# microphone_adapter_top.net
KiCad netlist of a schematic drawn in Altium Designer
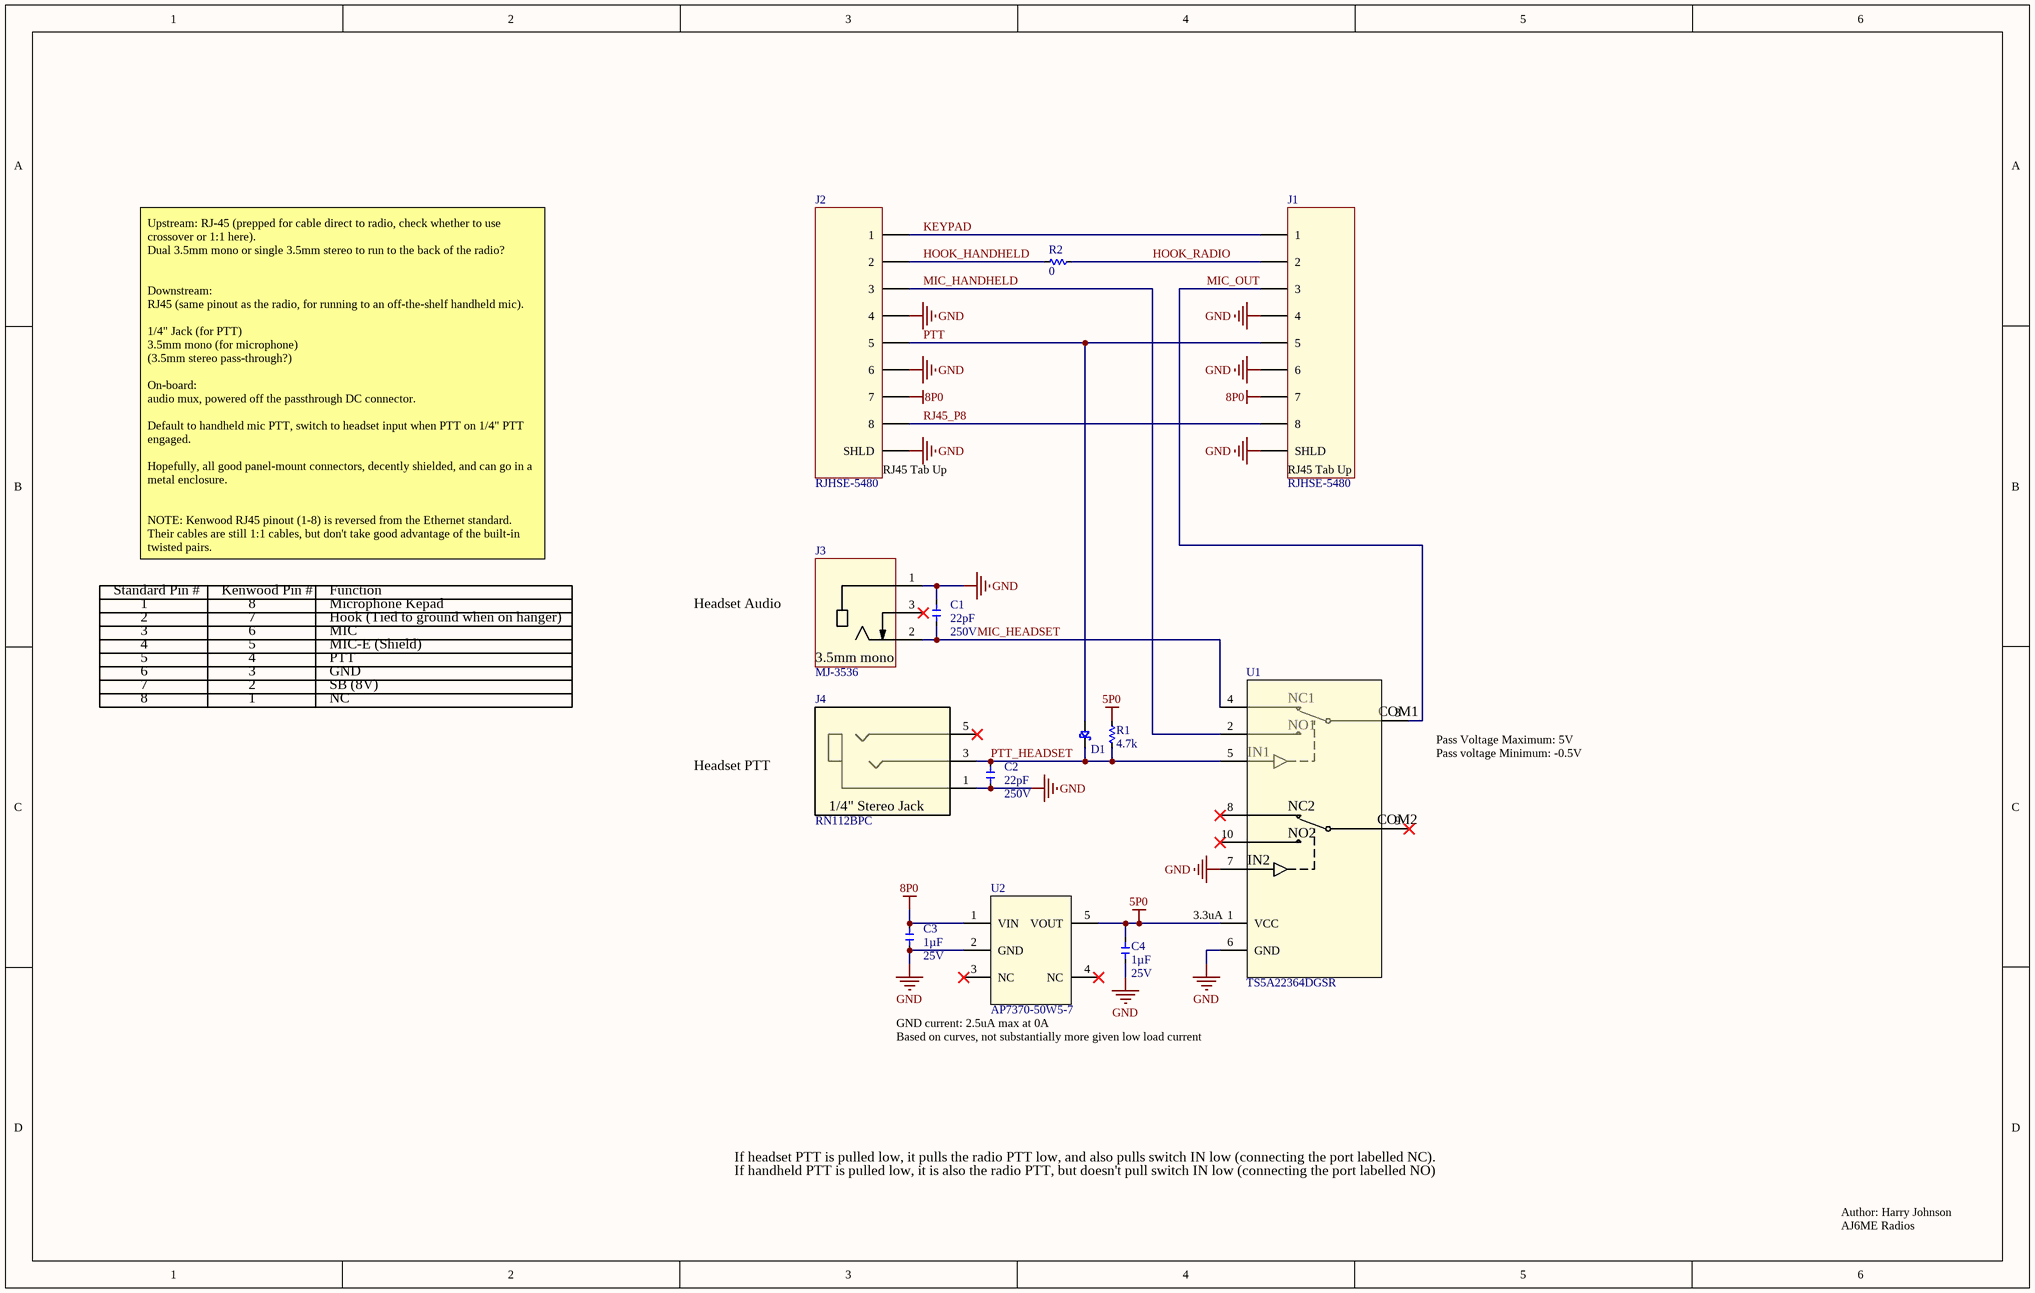
[diagram p0: microphone_adapter_top.SchDoc]

(export (version "E")
  (design (tool "Eeschema 10.0.6"))
  (components
    (comp (ref "C1")
      (value "GRM21A5C2E220JW01D")
      (footprint "C0805_1.00MM")
      (description "CAP CER 22PF 250V C0G/NP0 0805")
      (fields
        (field (name "CAPACITANCE") "22pF")
        (field (name "VOLTAGE - RATED") "250V")
        (field (name "DIGI-KEY PART NUMBER") "490-5534-1-ND")
        (field (name "MANUFACTURER") "Murata Electronics")
      )
      (libsource (lib "passives") (part "2pin_nonpolar_capacitor"))
    )
    (comp (ref "C2")
      (value "GRM21A5C2E220JW01D")
      (footprint "C0805_1.00MM")
      (description "CAP CER 22PF 250V C0G/NP0 0805")
      (fields
        (field (name "CAPACITANCE") "22pF")
        (field (name "VOLTAGE - RATED") "250V")
        (field (name "DIGI-KEY PART NUMBER") "490-5534-1-ND")
        (field (name "MANUFACTURER") "Murata Electronics")
      )
      (libsource (lib "passives") (part "2pin_nonpolar_capacitor"))
    )
    (comp (ref "C3")
      (value "GRM155C81E105ME11D")
      (footprint "C0402_0.55MM")
      (description "CAP CER 1UF 25V X6S 0402")
      (fields
        (field (name "CAPACITANCE") "1µF")
        (field (name "VOLTAGE - RATED") "25V")
        (field (name "DIGI-KEY PART NUMBER") "490-10015-1-ND")
        (field (name "MANUFACTURER") "Murata Electronics")
      )
      (libsource (lib "passives") (part "2pin_nonpolar_capacitor"))
    )
    (comp (ref "C4")
      (value "GRM155C81E105ME11D")
      (footprint "C0402_0.55MM")
      (description "CAP CER 1UF 25V X6S 0402")
      (fields
        (field (name "CAPACITANCE") "1µF")
        (field (name "VOLTAGE - RATED") "25V")
        (field (name "DIGI-KEY PART NUMBER") "490-10015-1-ND")
        (field (name "MANUFACTURER") "Murata Electronics")
      )
      (libsource (lib "passives") (part "2pin_nonpolar_capacitor"))
    )
    (comp (ref "D1")
      (value "BAT54XV2T1G")
      (footprint "SOD523_ONSEMI")
      (description "ON Semi BAT54XV2T1G; SMT Schottky Diode; 30V 200mA; 5ns; 2-Pin SOD-523")
      (fields (field (name "MANUFACTURER") "ON Semiconductor"))
      (libsource (lib "library") (part "DIODE_SCHOTTKY_30V_100MA_BAT54XV2T1G"))
    )
    (comp (ref "J1")
      (value "RJHSE-5480")
      (footprint "ETH_RJ45_RA_RJHSE-5480")
      (description "Conn RJ-45 F 8 POS 2.03mm Solder RA Thru-Hole 8 Terminal 1 Port Tray Cat 5")
      (fields (field (name "MANUFACTURER") "Amphenol"))
      (libsource (lib "") (part "CONN_ETH_RJ45_RA_SHLD_RJHSE-5480_ALT_1"))
    )
    (comp (ref "J2")
      (value "RJHSE-5480")
      (footprint "ETH_RJ45_RA_RJHSE-5480")
      (description "Conn RJ-45 F 8 POS 2.03mm Solder RA Thru-Hole 8 Terminal 1 Port Tray Cat 5")
      (fields (field (name "MANUFACTURER") "Amphenol"))
      (libsource (lib "library") (part "CONN_ETH_RJ45_RA_SHLD_RJHSE-5480_ALT"))
    )
    (comp (ref "J3")
      (value "MJ-3536")
      (footprint "AUD_CUI_MJ-3536")
      (description "CONN JACK MONO 3.5MM R/A")
      (fields (field (name "MANUFACTURER") "CUI"))
      (libsource (lib "library") (part "CONN_AUD_3.5_MM_MONO_MJ-3536"))
    )
    (comp (ref "J4")
      (value "RN112BPC")
      (footprint "AUD_SWITCHCRAFT_RN112BPC")
      (description "CONN JACK STEREO 0.25\" (6.35MM) R/A")
      (fields (field (name "MANUFACTURER") "Switchcraft"))
      (libsource (lib "library") (part "CONN_AUD_250_MIL_RN112BPC"))
    )
    (comp (ref "R1")
      (value "RC0402FR-074K7L")
      (footprint "R0402_0.40MM")
      (description "RES SMD 4.7K OHM 1% 1/16W 0402")
      (fields
        (field (name "RESISTANCE") "4.7k")
        (field (name "DIGI-KEY PART NUMBER") "311-4.7KLRCT-ND")
        (field (name "MANUFACTURER") "Yageo")
      )
      (libsource (lib "passives") (part "2pin_resistor"))
    )
    (comp (ref "R2")
      (value "RC0402JR-070RL")
      (footprint "R0402_0.40MM")
      (description "RES SMD 0 OHM JUMPER 1/16W 0402")
      (fields
        (field (name "RESISTANCE") "0")
        (field (name "DIGI-KEY PART NUMBER") "311-0.0JRCT-ND")
        (field (name "MANUFACTURER") "Yageo")
      )
      (libsource (lib "passives") (part "2pin_resistor"))
    )
    (comp (ref "U1")
      (value "TS5A22364DGSR")
      (footprint "TI_VSSOP_10_DGS0010A")
      (description "TEXAS INSTRUMENTS         TS5A22364DGSR.             ANALOG SWITCH, DUAL, SPDT, MSOP-10")
      (fields (field (name "MANUFACTURER") "Texas Instruments"))
      (libsource (lib "library") (part "IC_ANALOG_SWITCH_DUAL_SPDT_TS5A22364DGSR"))
    )
    (comp (ref "U2")
      (value "AP7370-50W5-7")
      (footprint "DIODES_INC_SOT25_5")
      (description "LDO Regulator Pos 5V 0.3A 5-Pin SOT-25 T/R")
      (fields (field (name "MANUFACTURER") "Diodes"))
      (libsource (lib "library") (part "LDO_5V_AP7370-50W5-7"))
    )
  )
  (nets
    (net (code "1") (name "/HOOK_HANDHELD") (class "Default")
      (node (ref "J2") (pin "2") (pinfunction "2_2") (pintype "passive"))
      (node (ref "R2") (pin "1") (pintype "passive"))
    )
    (net (code "2") (name "/HOOK_RADIO") (class "Default")
      (node (ref "J1") (pin "2") (pinfunction "2_2") (pintype "passive"))
      (node (ref "R2") (pin "2") (pintype "passive"))
    )
    (net (code "3") (name "/KEYPAD") (class "Default")
      (node (ref "J1") (pin "1") (pinfunction "1_1") (pintype "passive"))
      (node (ref "J2") (pin "1") (pinfunction "1_1") (pintype "passive"))
    )
    (net (code "4") (name "/MIC_HANDHELD") (class "Default")
      (node (ref "J2") (pin "3") (pinfunction "3_3") (pintype "passive"))
      (node (ref "U1") (pin "2") (pinfunction "NO1_2") (pintype "passive"))
    )
    (net (code "5") (name "/MIC_HEADSET") (class "Default")
      (node (ref "C1") (pin "2") (pintype "passive"))
      (node (ref "J3") (pin "2") (pinfunction "2_2") (pintype "passive"))
      (node (ref "U1") (pin "4") (pinfunction "NC1_4") (pintype "passive"))
    )
    (net (code "6") (name "/MIC_OUT") (class "Default")
      (node (ref "J1") (pin "3") (pinfunction "3_3") (pintype "passive"))
      (node (ref "U1") (pin "3") (pinfunction "COM1_3") (pintype "passive"))
    )
    (net (code "7") (name "/PTT") (class "Default")
      (node (ref "D1") (pin "2") (pintype "passive"))
      (node (ref "J1") (pin "5") (pinfunction "5_5") (pintype "passive"))
      (node (ref "J2") (pin "5") (pinfunction "5_5") (pintype "passive"))
    )
    (net (code "8") (name "/PTT_HEADSET") (class "Default")
      (node (ref "C2") (pin "1") (pintype "passive"))
      (node (ref "D1") (pin "1") (pintype "passive"))
      (node (ref "J4") (pin "3") (pinfunction "T_3") (pintype "passive"))
      (node (ref "R1") (pin "2") (pintype "passive"))
      (node (ref "U1") (pin "5") (pinfunction "IN1_5") (pintype "passive"))
    )
    (net (code "9") (name "/RJ45_P8") (class "Default")
      (node (ref "J1") (pin "8") (pinfunction "8_8") (pintype "passive"))
      (node (ref "J2") (pin "8") (pinfunction "8_8") (pintype "passive"))
    )
    (net (code "10") (name "5P0") (class "Default")
      (node (ref "C4") (pin "1") (pintype "passive"))
      (node (ref "R1") (pin "1") (pintype "passive"))
      (node (ref "U1") (pin "1") (pinfunction "VCC_1") (pintype "passive"))
      (node (ref "U2") (pin "5") (pinfunction "VOUT_5") (pintype "passive"))
    )
    (net (code "11") (name "8P0") (class "Default")
      (node (ref "C3") (pin "1") (pintype "passive"))
      (node (ref "J1") (pin "7") (pinfunction "7_7") (pintype "passive"))
      (node (ref "J2") (pin "7") (pinfunction "7_7") (pintype "passive"))
      (node (ref "U2") (pin "1") (pinfunction "VIN_1") (pintype "passive"))
    )
    (net (code "12") (name "GND") (class "Default")
      (node (ref "C1") (pin "1") (pintype "passive"))
      (node (ref "C2") (pin "2") (pintype "passive"))
      (node (ref "C3") (pin "2") (pintype "passive"))
      (node (ref "C4") (pin "2") (pintype "passive"))
      (node (ref "J1") (pin "4") (pinfunction "4_4") (pintype "passive"))
      (node (ref "J1") (pin "6") (pinfunction "6_6") (pintype "passive"))
      (node (ref "J1") (pin "SHLD") (pinfunction "SHLD_SHLD") (pintype "passive"))
      (node (ref "J2") (pin "4") (pinfunction "4_4") (pintype "passive"))
      (node (ref "J2") (pin "6") (pinfunction "6_6") (pintype "passive"))
      (node (ref "J2") (pin "SHLD") (pinfunction "SHLD_SHLD") (pintype "passive"))
      (node (ref "J3") (pin "1") (pinfunction "1_1") (pintype "passive"))
      (node (ref "J4") (pin "1") (pinfunction "S_1") (pintype "passive"))
      (node (ref "U1") (pin "6") (pinfunction "GND_6") (pintype "passive"))
      (node (ref "U1") (pin "7") (pinfunction "IN2_7") (pintype "passive"))
      (node (ref "U2") (pin "2") (pinfunction "GND_2") (pintype "passive"))
    )
    (net (code "13") (name "unconnected-(J3-Pad3)") (class "Default")
      (node (ref "J3") (pin "3") (pinfunction "3_3") (pintype "passive+no_connect"))
    )
    (net (code "14") (name "unconnected-(J4-R-Pad5)") (class "Default")
      (node (ref "J4") (pin "5") (pinfunction "R_5") (pintype "passive+no_connect"))
    )
    (net (code "15") (name "unconnected-(U1-COM2-Pad9)") (class "Default")
      (node (ref "U1") (pin "9") (pinfunction "COM2_9") (pintype "passive+no_connect"))
    )
    (net (code "16") (name "unconnected-(U1-NC2-Pad8)") (class "Default")
      (node (ref "U1") (pin "8") (pinfunction "NC2_8") (pintype "passive+no_connect"))
    )
    (net (code "17") (name "unconnected-(U1-NO2-Pad10)") (class "Default")
      (node (ref "U1") (pin "10") (pinfunction "NO2_10") (pintype "passive+no_connect"))
    )
    (net (code "18") (name "unconnected-(U2-NC-Pad3)") (class "Default")
      (node (ref "U2") (pin "3") (pinfunction "NC_3") (pintype "passive+no_connect"))
    )
    (net (code "19") (name "unconnected-(U2-NC-Pad4)") (class "Default")
      (node (ref "U2") (pin "4") (pinfunction "NC_4") (pintype "passive+no_connect"))
    )
  )
)
